# power_injector_rev_c.net
KiCad netlist of a schematic drawn in EAGLE
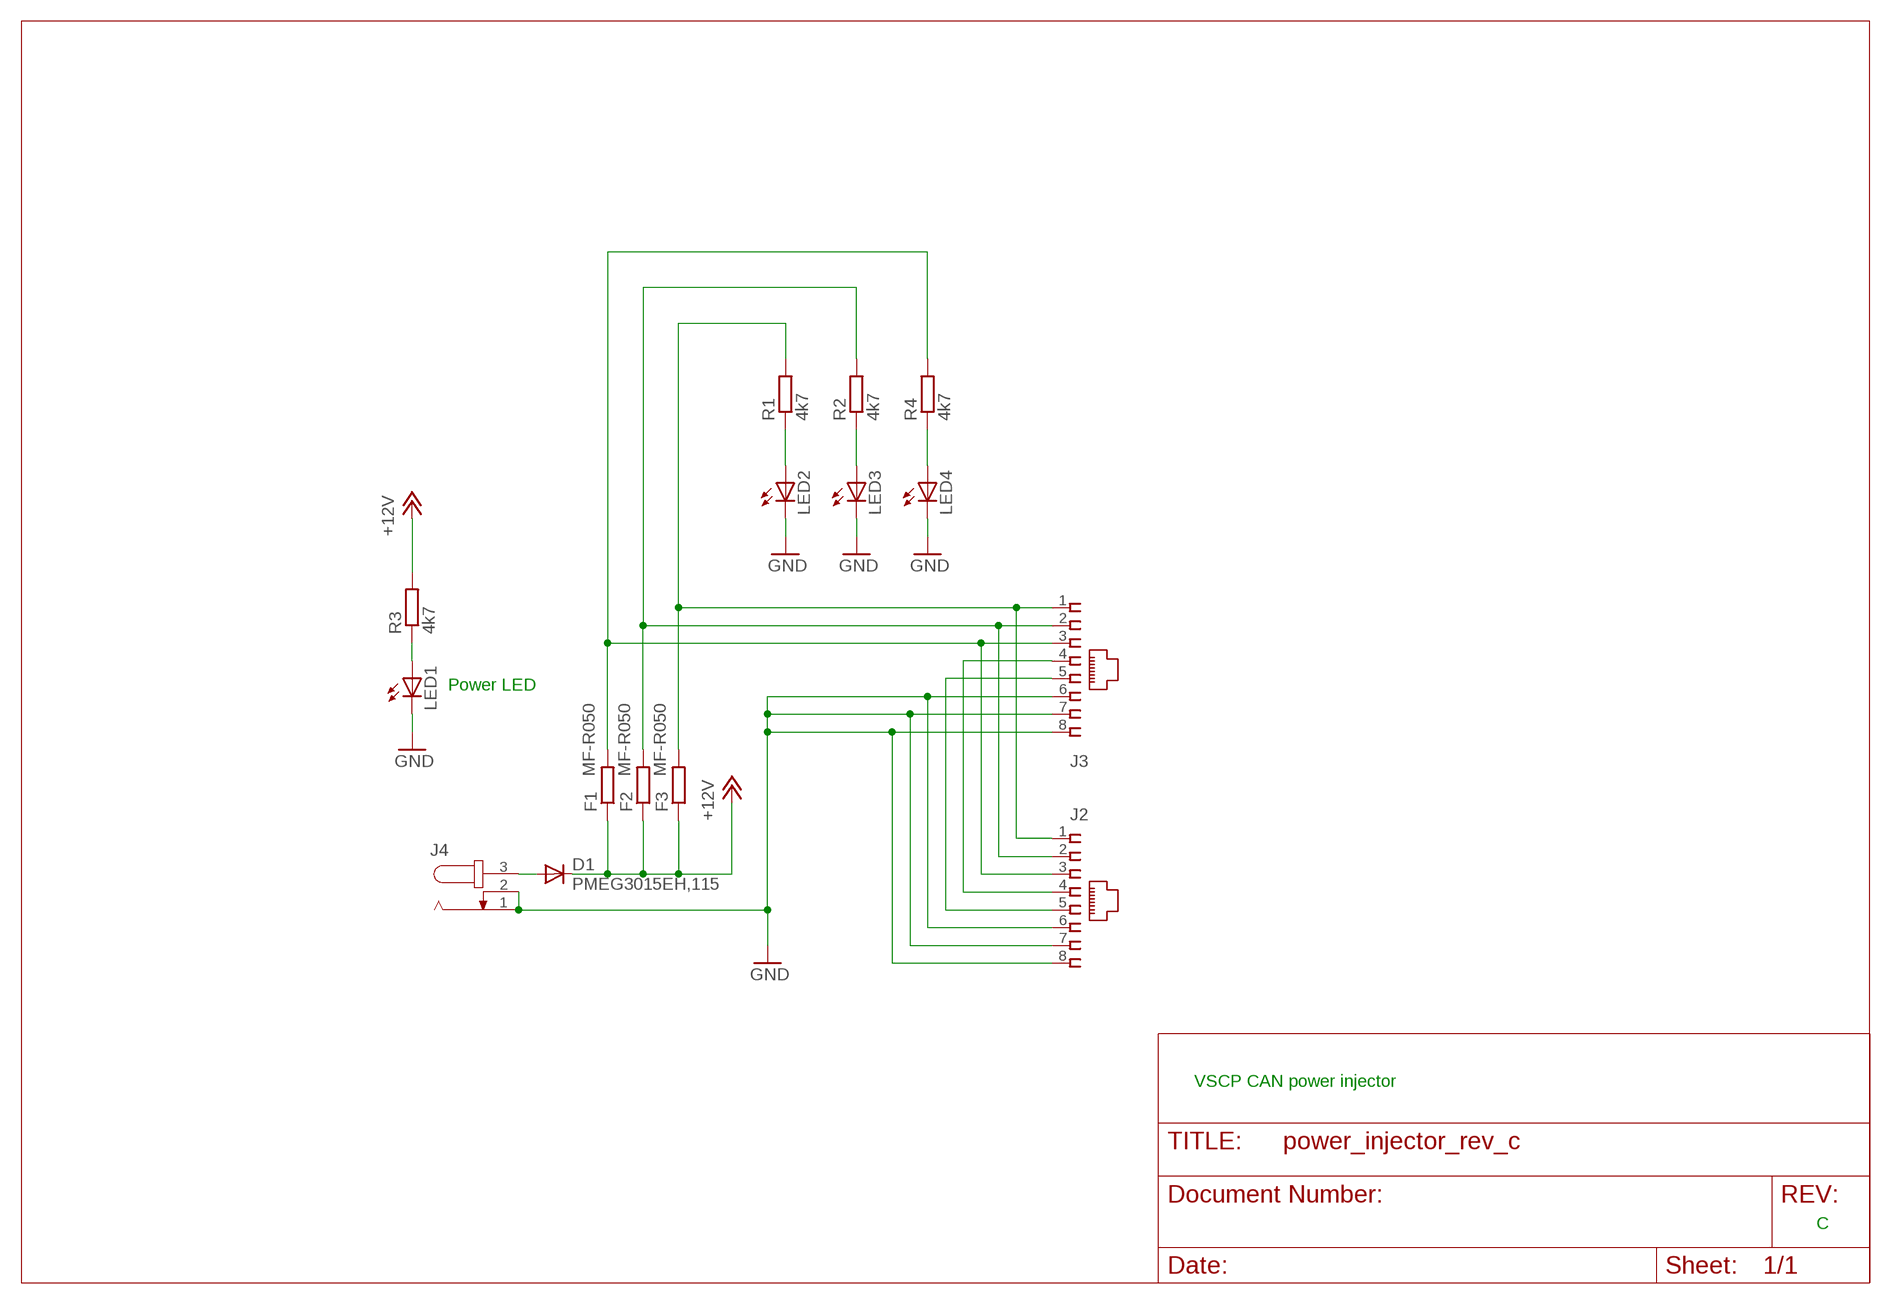
[diagram p0: schematic, sheet 1]

(export (version "E")
  (design (tool "Eeschema 10.0.6"))
  (components
    (comp (ref "D1")
      (value "PMEG3015EH,115")
      (footprint "eagle-import:SMB")
      (libsource (lib "eagle-import") (part "DIODE-SMB"))
    )
    (comp (ref "F1")
      (value "MF-R050")
      (footprint "eagle-import:0204_5")
      (libsource (lib "eagle-import") (part "R-EU_0204/5"))
    )
    (comp (ref "F2")
      (value "MF-R050")
      (footprint "eagle-import:0204_5")
      (libsource (lib "eagle-import") (part "R-EU_0204/5"))
    )
    (comp (ref "F3")
      (value "MF-R050")
      (footprint "eagle-import:0204_5")
      (libsource (lib "eagle-import") (part "R-EU_0204/5"))
    )
    (comp (ref "J2")
      (value "A00-108-220-450")
      (footprint "eagle-import:RJ-45")
      (libsource (lib "eagle-import") (part "A00-108-220-450"))
    )
    (comp (ref "J3")
      (value "A00-108-220-450")
      (footprint "eagle-import:RJ-45")
      (libsource (lib "eagle-import") (part "A00-108-220-450"))
    )
    (comp (ref "J4")
      (value "JACK-PLUG0")
      (footprint "eagle-import:SPC4077")
      (libsource (lib "eagle-import") (part "JACK-PLUG0"))
    )
    (comp (ref "LED1")
      (value "LEDCHIP-LED0805")
      (footprint "eagle-import:CHIP-LED0805")
      (libsource (lib "eagle-import") (part "LEDCHIP-LED0805"))
    )
    (comp (ref "LED2")
      (value "LEDCHIP-LED0805")
      (footprint "eagle-import:CHIP-LED0805")
      (libsource (lib "eagle-import") (part "LEDCHIP-LED0805"))
    )
    (comp (ref "LED3")
      (value "LEDCHIP-LED0805")
      (footprint "eagle-import:CHIP-LED0805")
      (libsource (lib "eagle-import") (part "LEDCHIP-LED0805"))
    )
    (comp (ref "LED4")
      (value "LEDCHIP-LED0805")
      (footprint "eagle-import:CHIP-LED0805")
      (libsource (lib "eagle-import") (part "LEDCHIP-LED0805"))
    )
    (comp (ref "R1")
      (value "4k7")
      (footprint "eagle-import:R0805")
      (libsource (lib "eagle-import") (part "R-EU_R0805"))
    )
    (comp (ref "R2")
      (value "4k7")
      (footprint "eagle-import:R0805")
      (libsource (lib "eagle-import") (part "R-EU_R0805"))
    )
    (comp (ref "R3")
      (value "4k7")
      (footprint "eagle-import:R0805")
      (libsource (lib "eagle-import") (part "R-EU_R0805"))
    )
    (comp (ref "R4")
      (value "4k7")
      (footprint "eagle-import:R0805")
      (libsource (lib "eagle-import") (part "R-EU_R0805"))
    )
  )
  (nets
    (net (code "1") (name "+12V") (class "Default")
      (node (ref "D1") (pin "C") (pinfunction "C_C") (pintype "passive"))
      (node (ref "F1") (pin "1") (pinfunction "1_1") (pintype "passive"))
      (node (ref "F2") (pin "1") (pinfunction "1_1") (pintype "passive"))
      (node (ref "F3") (pin "1") (pinfunction "1_1") (pintype "passive"))
      (node (ref "R3") (pin "2") (pinfunction "2_2") (pintype "passive"))
    )
    (net (code "2") (name "GND") (class "Default")
      (node (ref "J2") (pin "6") (pinfunction "6_6") (pintype "passive"))
      (node (ref "J2") (pin "7") (pinfunction "7_7") (pintype "passive"))
      (node (ref "J2") (pin "8") (pinfunction "8_8") (pintype "passive"))
      (node (ref "J3") (pin "6") (pinfunction "6_6") (pintype "passive"))
      (node (ref "J3") (pin "7") (pinfunction "7_7") (pintype "passive"))
      (node (ref "J3") (pin "8") (pinfunction "8_8") (pintype "passive"))
      (node (ref "J4") (pin "1") (pinfunction "1_1") (pintype "passive"))
      (node (ref "J4") (pin "2") (pinfunction "2_2") (pintype "passive"))
      (node (ref "LED1") (pin "C") (pinfunction "C_C") (pintype "passive"))
      (node (ref "LED2") (pin "C") (pinfunction "C_C") (pintype "passive"))
      (node (ref "LED3") (pin "C") (pinfunction "C_C") (pintype "passive"))
      (node (ref "LED4") (pin "C") (pinfunction "C_C") (pintype "passive"))
    )
    (net (code "3") (name "Net-(D1-PadA)") (class "Default")
      (node (ref "D1") (pin "A") (pinfunction "A_A") (pintype "passive"))
      (node (ref "J4") (pin "3") (pinfunction "3_3") (pintype "passive"))
    )
    (net (code "4") (name "Net-(F1-Pad2)") (class "Default")
      (node (ref "F1") (pin "2") (pinfunction "2_2") (pintype "passive"))
      (node (ref "J2") (pin "3") (pinfunction "3_3") (pintype "passive"))
      (node (ref "J3") (pin "3") (pinfunction "3_3") (pintype "passive"))
      (node (ref "R4") (pin "2") (pinfunction "2_2") (pintype "passive"))
    )
    (net (code "5") (name "Net-(F2-Pad2)") (class "Default")
      (node (ref "F2") (pin "2") (pinfunction "2_2") (pintype "passive"))
      (node (ref "J2") (pin "2") (pinfunction "2_2") (pintype "passive"))
      (node (ref "J3") (pin "2") (pinfunction "2_2") (pintype "passive"))
      (node (ref "R2") (pin "2") (pinfunction "2_2") (pintype "passive"))
    )
    (net (code "6") (name "Net-(F3-Pad2)") (class "Default")
      (node (ref "F3") (pin "2") (pinfunction "2_2") (pintype "passive"))
      (node (ref "J2") (pin "1") (pinfunction "1_1") (pintype "passive"))
      (node (ref "J3") (pin "1") (pinfunction "1_1") (pintype "passive"))
      (node (ref "R1") (pin "2") (pinfunction "2_2") (pintype "passive"))
    )
    (net (code "7") (name "Net-(J2-Pad4)") (class "Default")
      (node (ref "J2") (pin "4") (pinfunction "4_4") (pintype "passive"))
      (node (ref "J3") (pin "4") (pinfunction "4_4") (pintype "passive"))
    )
    (net (code "8") (name "Net-(J2-Pad5)") (class "Default")
      (node (ref "J2") (pin "5") (pinfunction "5_5") (pintype "passive"))
      (node (ref "J3") (pin "5") (pinfunction "5_5") (pintype "passive"))
    )
    (net (code "9") (name "Net-(LED1-PadA)") (class "Default")
      (node (ref "LED1") (pin "A") (pinfunction "A_A") (pintype "passive"))
      (node (ref "R3") (pin "1") (pinfunction "1_1") (pintype "passive"))
    )
    (net (code "10") (name "Net-(LED2-PadA)") (class "Default")
      (node (ref "LED2") (pin "A") (pinfunction "A_A") (pintype "passive"))
      (node (ref "R1") (pin "1") (pinfunction "1_1") (pintype "passive"))
    )
    (net (code "11") (name "Net-(LED3-PadA)") (class "Default")
      (node (ref "LED3") (pin "A") (pinfunction "A_A") (pintype "passive"))
      (node (ref "R2") (pin "1") (pinfunction "1_1") (pintype "passive"))
    )
    (net (code "12") (name "Net-(LED4-PadA)") (class "Default")
      (node (ref "LED4") (pin "A") (pinfunction "A_A") (pintype "passive"))
      (node (ref "R4") (pin "1") (pinfunction "1_1") (pintype "passive"))
    )
  )
)
